# arduino_shield_out.net
KiCad netlist of a schematic drawn in EAGLE
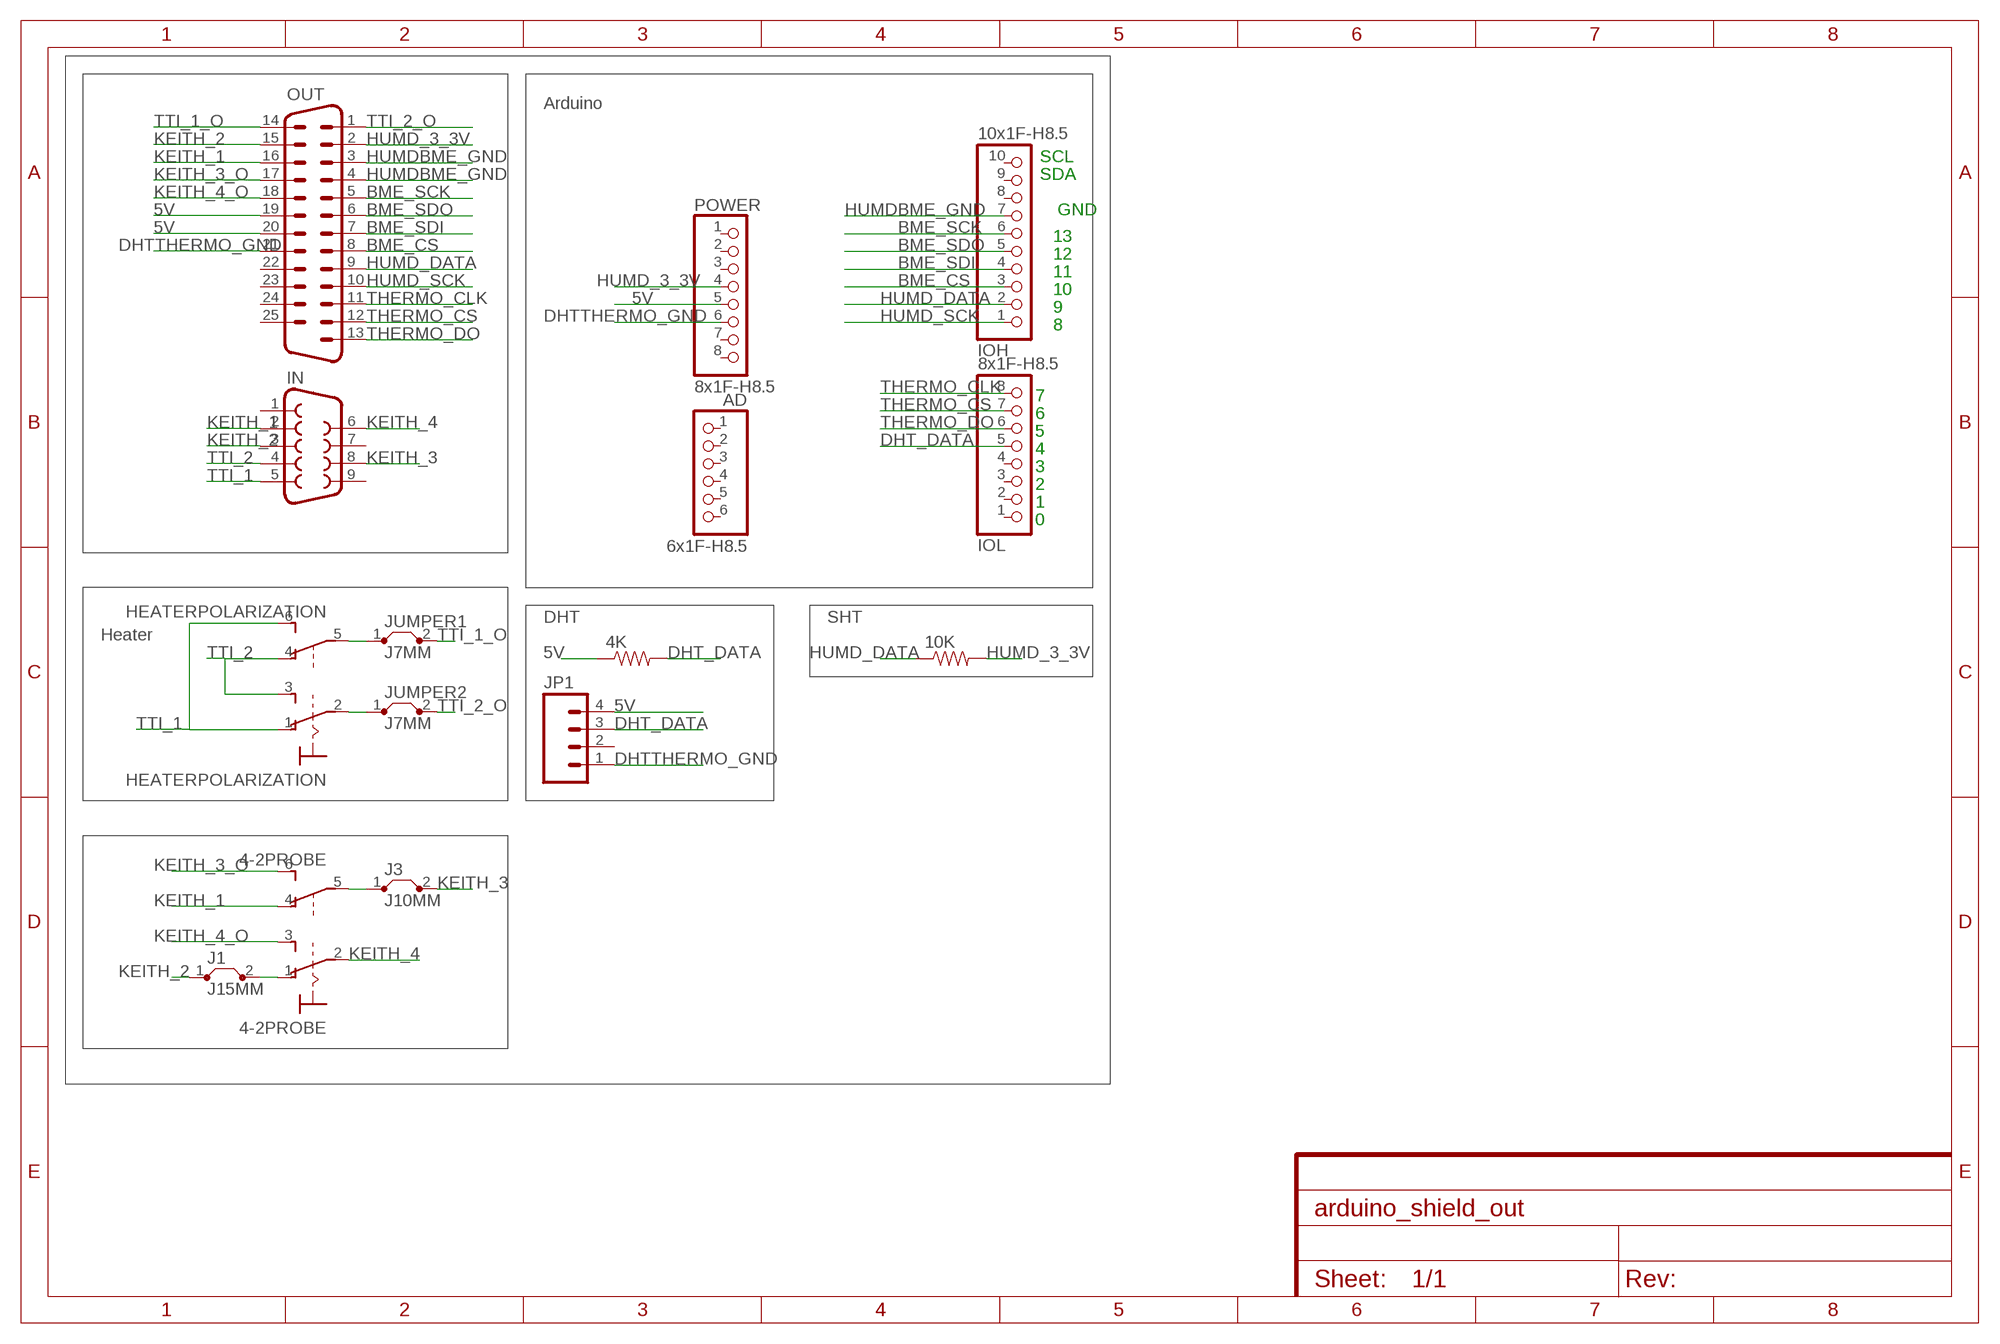
[diagram p0: schematic, sheet 1]

(export (version "E")
  (design (tool "Eeschema 10.0.6"))
  (components
    (comp (ref "4-2PROBE")
      (value "M9040P2")
      (footprint "eagle-import:M9040P2")
      (libsource (lib "eagle-import") (part "M9040P2"))
    )
    (comp (ref "4K")
      (value "RESISTORPTH-1/2W")
      (footprint "eagle-import:AXIAL-0.5")
      (libsource (lib "eagle-import") (part "RESISTORPTH-1/2W"))
    )
    (comp (ref "10K")
      (value "RESISTORKIT")
      (footprint "eagle-import:AXIAL-0.3-KIT")
      (libsource (lib "eagle-import") (part "RESISTORKIT"))
    )
    (comp (ref "AD")
      (value "6x1F-H8.5")
      (footprint "eagle-import:1X06")
      (libsource (lib "eagle-import") (part "PINHD-1X6"))
    )
    (comp (ref "HEATERPOLARIZATION")
      (value "M9040P2")
      (footprint "eagle-import:M9040P2")
      (libsource (lib "eagle-import") (part "M9040P2"))
    )
    (comp (ref "IN")
      (value "DB9FEMALE")
      (footprint "eagle-import:DB9")
      (libsource (lib "eagle-import") (part "DB9FEMALE"))
    )
    (comp (ref "IOH")
      (value "10x1F-H8.5")
      (footprint "eagle-import:1X10")
      (libsource (lib "eagle-import") (part "PINHD-1X10_ARD"))
    )
    (comp (ref "IOL")
      (value "8x1F-H8.5")
      (footprint "eagle-import:1X08")
      (libsource (lib "eagle-import") (part "PINHD-1X8"))
    )
    (comp (ref "J1")
      (value "J15MM")
      (footprint "eagle-import:15")
      (libsource (lib "eagle-import") (part "J15MM"))
    )
    (comp (ref "J3")
      (value "J10MM")
      (footprint "eagle-import:10")
      (libsource (lib "eagle-import") (part "J10MM"))
    )
    (comp (ref "JP1")
      (value "M04PTH")
      (footprint "eagle-import:1X04")
      (libsource (lib "eagle-import") (part "M04PTH"))
    )
    (comp (ref "JUMPER1")
      (value "J7MM")
      (footprint "eagle-import:07")
      (libsource (lib "eagle-import") (part "J7MM"))
    )
    (comp (ref "JUMPER2")
      (value "J7MM")
      (footprint "eagle-import:07")
      (libsource (lib "eagle-import") (part "J7MM"))
    )
    (comp (ref "OUT")
      (value "DB25V")
      (footprint "eagle-import:M25V")
      (libsource (lib "eagle-import") (part "DB25V"))
    )
    (comp (ref "POWER")
      (value "8x1F-H8.5")
      (footprint "eagle-import:1X08")
      (libsource (lib "eagle-import") (part "PINHD-1X8"))
    )
  )
  (nets
    (net (code "1") (name "/5V") (class "Default")
      (node (ref "4K") (pin "P$1") (pinfunction "1_P$1") (pintype "passive"))
      (node (ref "JP1") (pin "4") (pinfunction "4_4") (pintype "passive"))
      (node (ref "OUT") (pin "19") (pinfunction "19_19") (pintype "passive"))
      (node (ref "OUT") (pin "20") (pinfunction "20_20") (pintype "passive"))
      (node (ref "POWER") (pin "5") (pinfunction "5_5") (pintype "passive"))
    )
    (net (code "2") (name "/BME_CS") (class "Default")
      (node (ref "IOH") (pin "3") (pinfunction "3_3") (pintype "passive"))
      (node (ref "OUT") (pin "8") (pinfunction "8_8") (pintype "passive"))
    )
    (net (code "3") (name "/BME_SCK") (class "Default")
      (node (ref "IOH") (pin "6") (pinfunction "6_6") (pintype "passive"))
      (node (ref "OUT") (pin "5") (pinfunction "5_5") (pintype "passive"))
    )
    (net (code "4") (name "/BME_SDI") (class "Default")
      (node (ref "IOH") (pin "4") (pinfunction "4_4") (pintype "passive"))
      (node (ref "OUT") (pin "7") (pinfunction "7_7") (pintype "passive"))
    )
    (net (code "5") (name "/BME_SDO") (class "Default")
      (node (ref "IOH") (pin "5") (pinfunction "5_5") (pintype "passive"))
      (node (ref "OUT") (pin "6") (pinfunction "6_6") (pintype "passive"))
    )
    (net (code "6") (name "/DHTTHERMO_GND") (class "Default")
      (node (ref "JP1") (pin "1") (pinfunction "1_1") (pintype "passive"))
      (node (ref "OUT") (pin "21") (pinfunction "21_21") (pintype "passive"))
      (node (ref "POWER") (pin "6") (pinfunction "6_6") (pintype "passive"))
    )
    (net (code "7") (name "/DHT_DATA") (class "Default")
      (node (ref "4K") (pin "P$2") (pinfunction "2_P$2") (pintype "passive"))
      (node (ref "IOL") (pin "5") (pinfunction "5_5") (pintype "passive"))
      (node (ref "JP1") (pin "3") (pinfunction "3_3") (pintype "passive"))
    )
    (net (code "8") (name "/HUMDBME_GND") (class "Default")
      (node (ref "IOH") (pin "7") (pinfunction "7_7") (pintype "passive"))
      (node (ref "OUT") (pin "3") (pinfunction "3_3") (pintype "passive"))
      (node (ref "OUT") (pin "4") (pinfunction "4_4") (pintype "passive"))
    )
    (net (code "9") (name "/HUMD_3_3V") (class "Default")
      (node (ref "10K") (pin "P$2") (pinfunction "2_P$2") (pintype "passive"))
      (node (ref "OUT") (pin "2") (pinfunction "2_2") (pintype "passive"))
      (node (ref "POWER") (pin "4") (pinfunction "4_4") (pintype "passive"))
    )
    (net (code "10") (name "/HUMD_DATA") (class "Default")
      (node (ref "10K") (pin "P$1") (pinfunction "1_P$1") (pintype "passive"))
      (node (ref "IOH") (pin "2") (pinfunction "2_2") (pintype "passive"))
      (node (ref "OUT") (pin "9") (pinfunction "9_9") (pintype "passive"))
    )
    (net (code "11") (name "/HUMD_SCK") (class "Default")
      (node (ref "IOH") (pin "1") (pinfunction "1_1") (pintype "passive"))
      (node (ref "OUT") (pin "10") (pinfunction "10_10") (pintype "passive"))
    )
    (net (code "12") (name "/KEITH_1") (class "Default")
      (node (ref "4-2PROBE") (pin "4") (pinfunction "O_4") (pintype "passive"))
      (node (ref "IN") (pin "2") (pinfunction "2_2") (pintype "passive"))
      (node (ref "OUT") (pin "16") (pinfunction "16_16") (pintype "passive"))
    )
    (net (code "13") (name "/KEITH_2") (class "Default")
      (node (ref "IN") (pin "3") (pinfunction "3_3") (pintype "passive"))
      (node (ref "J1") (pin "1") (pinfunction "1_1") (pintype "passive"))
      (node (ref "OUT") (pin "15") (pinfunction "15_15") (pintype "passive"))
    )
    (net (code "14") (name "/KEITH_3") (class "Default")
      (node (ref "IN") (pin "8") (pinfunction "8_8") (pintype "passive"))
      (node (ref "J3") (pin "2") (pinfunction "2_2") (pintype "passive"))
    )
    (net (code "15") (name "/KEITH_3_O") (class "Default")
      (node (ref "4-2PROBE") (pin "6") (pinfunction "S_6") (pintype "passive"))
      (node (ref "OUT") (pin "17") (pinfunction "17_17") (pintype "passive"))
    )
    (net (code "16") (name "/KEITH_4") (class "Default")
      (node (ref "4-2PROBE") (pin "2") (pinfunction "P_2") (pintype "passive"))
      (node (ref "IN") (pin "6") (pinfunction "6_6") (pintype "passive"))
    )
    (net (code "17") (name "/KEITH_4_O") (class "Default")
      (node (ref "4-2PROBE") (pin "3") (pinfunction "S_3") (pintype "passive"))
      (node (ref "OUT") (pin "18") (pinfunction "18_18") (pintype "passive"))
    )
    (net (code "18") (name "/THERMO_CLK") (class "Default")
      (node (ref "IOL") (pin "8") (pinfunction "8_8") (pintype "passive"))
      (node (ref "OUT") (pin "11") (pinfunction "11_11") (pintype "passive"))
    )
    (net (code "19") (name "/THERMO_CS") (class "Default")
      (node (ref "IOL") (pin "7") (pinfunction "7_7") (pintype "passive"))
      (node (ref "OUT") (pin "12") (pinfunction "12_12") (pintype "passive"))
    )
    (net (code "20") (name "/THERMO_DO") (class "Default")
      (node (ref "IOL") (pin "6") (pinfunction "6_6") (pintype "passive"))
      (node (ref "OUT") (pin "13") (pinfunction "13_13") (pintype "passive"))
    )
    (net (code "21") (name "/TTI_1") (class "Default")
      (node (ref "HEATERPOLARIZATION") (pin "1") (pinfunction "O_1") (pintype "passive"))
      (node (ref "HEATERPOLARIZATION") (pin "6") (pinfunction "S_6") (pintype "passive"))
      (node (ref "IN") (pin "5") (pinfunction "5_5") (pintype "passive"))
    )
    (net (code "22") (name "/TTI_1_O") (class "Default")
      (node (ref "JUMPER1") (pin "2") (pinfunction "2_2") (pintype "passive"))
      (node (ref "OUT") (pin "14") (pinfunction "14_14") (pintype "passive"))
    )
    (net (code "23") (name "/TTI_2") (class "Default")
      (node (ref "HEATERPOLARIZATION") (pin "3") (pinfunction "S_3") (pintype "passive"))
      (node (ref "HEATERPOLARIZATION") (pin "4") (pinfunction "O_4") (pintype "passive"))
      (node (ref "IN") (pin "4") (pinfunction "4_4") (pintype "passive"))
    )
    (net (code "24") (name "/TTI_2_O") (class "Default")
      (node (ref "JUMPER2") (pin "2") (pinfunction "2_2") (pintype "passive"))
      (node (ref "OUT") (pin "1") (pinfunction "1_1") (pintype "passive"))
    )
    (net (code "25") (name "Net-(4-2PROBEA-O)") (class "Default")
      (node (ref "4-2PROBE") (pin "1") (pinfunction "O_1") (pintype "passive"))
      (node (ref "J1") (pin "2") (pinfunction "2_2") (pintype "passive"))
    )
    (net (code "26") (name "Net-(4-2PROBEB-P)") (class "Default")
      (node (ref "4-2PROBE") (pin "5") (pinfunction "P_5") (pintype "passive"))
      (node (ref "J3") (pin "1") (pinfunction "1_1") (pintype "passive"))
    )
    (net (code "27") (name "Net-(HEATERPOLARIZATIONA-P)") (class "Default")
      (node (ref "HEATERPOLARIZATION") (pin "2") (pinfunction "P_2") (pintype "passive"))
      (node (ref "JUMPER2") (pin "1") (pinfunction "1_1") (pintype "passive"))
    )
    (net (code "28") (name "Net-(HEATERPOLARIZATIONB-P)") (class "Default")
      (node (ref "HEATERPOLARIZATION") (pin "5") (pinfunction "P_5") (pintype "passive"))
      (node (ref "JUMPER1") (pin "1") (pinfunction "1_1") (pintype "passive"))
    )
    (net (code "29") (name "unconnected-(AD-Pad1)") (class "Default")
      (node (ref "AD") (pin "1") (pinfunction "1_1") (pintype "passive"))
    )
    (net (code "30") (name "unconnected-(AD-Pad2)") (class "Default")
      (node (ref "AD") (pin "2") (pinfunction "2_2") (pintype "passive"))
    )
    (net (code "31") (name "unconnected-(AD-Pad3)") (class "Default")
      (node (ref "AD") (pin "3") (pinfunction "3_3") (pintype "passive"))
    )
    (net (code "32") (name "unconnected-(AD-Pad4)") (class "Default")
      (node (ref "AD") (pin "4") (pinfunction "4_4") (pintype "passive"))
    )
    (net (code "33") (name "unconnected-(AD-Pad5)") (class "Default")
      (node (ref "AD") (pin "5") (pinfunction "5_5") (pintype "passive"))
    )
    (net (code "34") (name "unconnected-(AD-Pad6)") (class "Default")
      (node (ref "AD") (pin "6") (pinfunction "6_6") (pintype "passive"))
    )
    (net (code "35") (name "unconnected-(IN-Pad1)") (class "Default")
      (node (ref "IN") (pin "1") (pinfunction "1_1") (pintype "passive"))
    )
    (net (code "36") (name "unconnected-(IN-Pad7)") (class "Default")
      (node (ref "IN") (pin "7") (pinfunction "7_7") (pintype "passive"))
    )
    (net (code "37") (name "unconnected-(IN-Pad9)") (class "Default")
      (node (ref "IN") (pin "9") (pinfunction "9_9") (pintype "passive"))
    )
    (net (code "38") (name "unconnected-(IOH-Pad8)") (class "Default")
      (node (ref "IOH") (pin "8") (pinfunction "8_8") (pintype "passive"))
    )
    (net (code "39") (name "unconnected-(IOH-Pad9)") (class "Default")
      (node (ref "IOH") (pin "9") (pinfunction "9_9") (pintype "passive"))
    )
    (net (code "40") (name "unconnected-(IOH-Pad10)") (class "Default")
      (node (ref "IOH") (pin "10") (pinfunction "10_10") (pintype "passive"))
    )
    (net (code "41") (name "unconnected-(IOL-Pad1)") (class "Default")
      (node (ref "IOL") (pin "1") (pinfunction "1_1") (pintype "passive"))
    )
    (net (code "42") (name "unconnected-(IOL-Pad2)") (class "Default")
      (node (ref "IOL") (pin "2") (pinfunction "2_2") (pintype "passive"))
    )
    (net (code "43") (name "unconnected-(IOL-Pad3)") (class "Default")
      (node (ref "IOL") (pin "3") (pinfunction "3_3") (pintype "passive"))
    )
    (net (code "44") (name "unconnected-(IOL-Pad4)") (class "Default")
      (node (ref "IOL") (pin "4") (pinfunction "4_4") (pintype "passive"))
    )
    (net (code "45") (name "unconnected-(JP1-Pad2)") (class "Default")
      (node (ref "JP1") (pin "2") (pinfunction "2_2") (pintype "passive"))
    )
    (net (code "46") (name "unconnected-(OUT-Pad22)") (class "Default")
      (node (ref "OUT") (pin "22") (pinfunction "22_22") (pintype "passive"))
    )
    (net (code "47") (name "unconnected-(OUT-Pad23)") (class "Default")
      (node (ref "OUT") (pin "23") (pinfunction "23_23") (pintype "passive"))
    )
    (net (code "48") (name "unconnected-(OUT-Pad24)") (class "Default")
      (node (ref "OUT") (pin "24") (pinfunction "24_24") (pintype "passive"))
    )
    (net (code "49") (name "unconnected-(OUT-Pad25)") (class "Default")
      (node (ref "OUT") (pin "25") (pinfunction "25_25") (pintype "passive"))
    )
    (net (code "50") (name "unconnected-(POWER-Pad1)") (class "Default")
      (node (ref "POWER") (pin "1") (pinfunction "1_1") (pintype "passive"))
    )
    (net (code "51") (name "unconnected-(POWER-Pad2)") (class "Default")
      (node (ref "POWER") (pin "2") (pinfunction "2_2") (pintype "passive"))
    )
    (net (code "52") (name "unconnected-(POWER-Pad3)") (class "Default")
      (node (ref "POWER") (pin "3") (pinfunction "3_3") (pintype "passive"))
    )
    (net (code "53") (name "unconnected-(POWER-Pad7)") (class "Default")
      (node (ref "POWER") (pin "7") (pinfunction "7_7") (pintype "passive"))
    )
    (net (code "54") (name "unconnected-(POWER-Pad8)") (class "Default")
      (node (ref "POWER") (pin "8") (pinfunction "8_8") (pintype "passive"))
    )
  )
)
